# power.net
KiCad netlist of a schematic drawn in Altium Designer
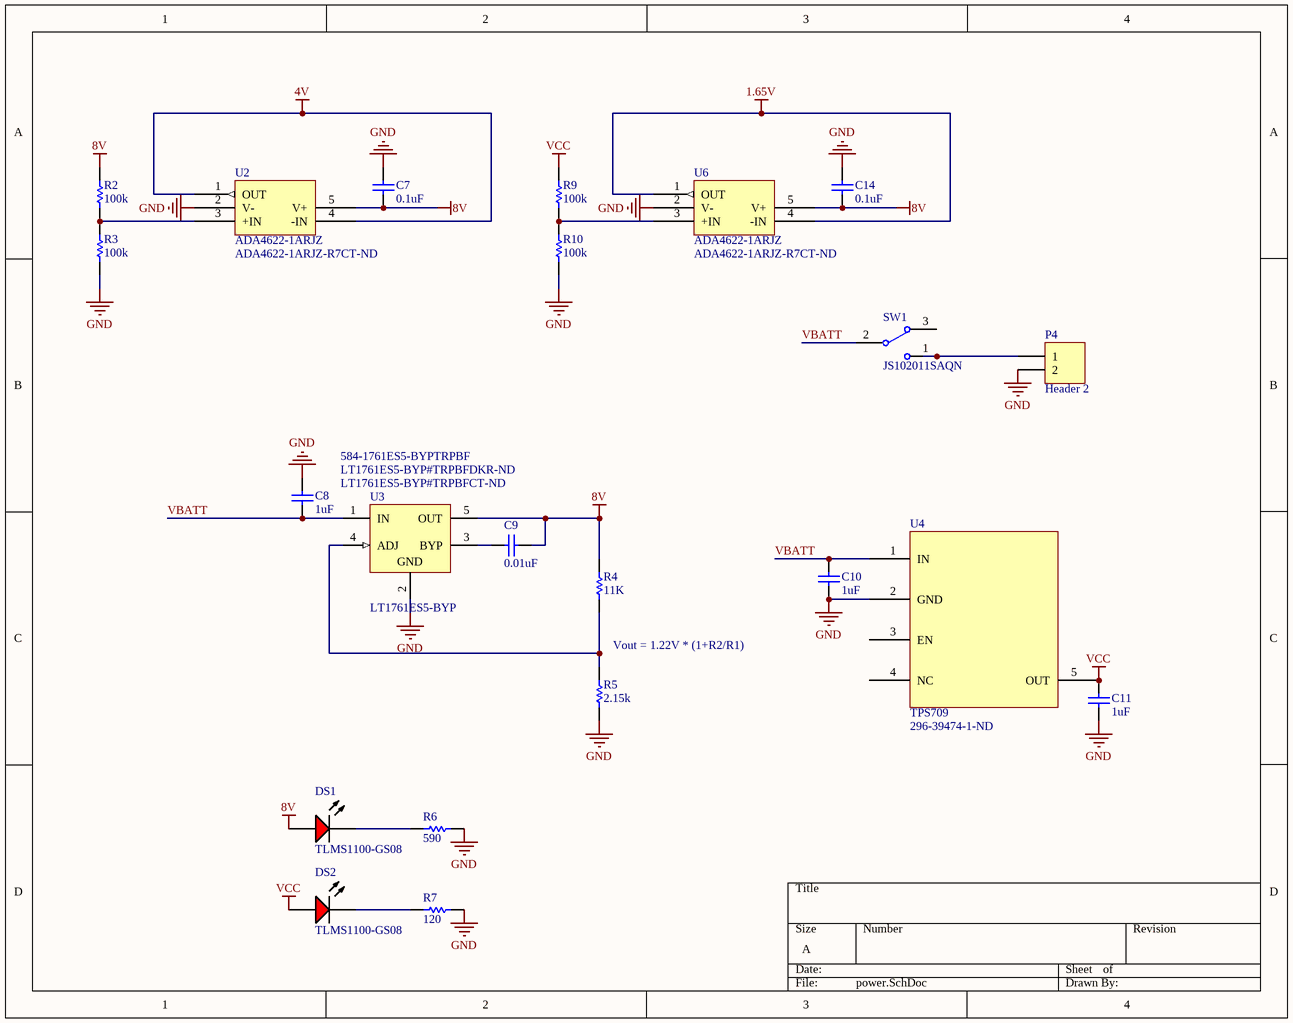
[diagram p0: power.SchDoc]

(export (version "E")
  (design (tool "Eeschema 10.0.6"))
  (components
    (comp (ref "C7")
      (value "0.1uF")
      (footprint "0603")
      (description "Ceramic Capacitor (Surface Mount)")
      (fields (field (name "MANUFACTURER") "Generic Ceramic Chip Cap (TBD)") (field (name "Comment") "Cap"))
      (libsource (lib "maglib") (part "Cap"))
    )
    (comp (ref "C8")
      (value "1uF")
      (footprint "0603")
      (description "Ceramic Capacitor (Surface Mount)")
      (fields (field (name "MANUFACTURER") "Generic Ceramic Chip Cap (TBD)") (field (name "Comment") "Cap"))
      (libsource (lib "maglib") (part "Cap"))
    )
    (comp (ref "C9")
      (value "0.01uF")
      (footprint "0603")
      (description "Ceramic Capacitor (Surface Mount)")
      (fields (field (name "MANUFACTURER") "Generic Ceramic Chip Cap (TBD)") (field (name "Comment") "Cap"))
      (libsource (lib "maglib") (part "Cap"))
    )
    (comp (ref "C10")
      (value "1uF")
      (footprint "0603")
      (description "Ceramic Capacitor (Surface Mount)")
      (fields (field (name "MANUFACTURER") "Generic Ceramic Chip Cap (TBD)") (field (name "Comment") "Cap"))
      (libsource (lib "maglib") (part "Cap"))
    )
    (comp (ref "C11")
      (value "1uF")
      (footprint "0603")
      (description "Ceramic Capacitor (Surface Mount)")
      (fields (field (name "MANUFACTURER") "Generic Ceramic Chip Cap (TBD)") (field (name "Comment") "Cap"))
      (libsource (lib "maglib") (part "Cap"))
    )
    (comp (ref "C14")
      (value "0.1uF")
      (footprint "0603")
      (description "Ceramic Capacitor (Surface Mount)")
      (fields (field (name "MANUFACTURER") "Generic Ceramic Chip Cap (TBD)") (field (name "Comment") "Cap"))
      (libsource (lib "maglib") (part "Cap"))
    )
    (comp (ref "DS1")
      (value "TLMS1100-GS08")
      (footprint "VISH-TLMX1100_V")
      (description "LED, RED, 2.1 V, -40 to 100 degC, 2-Pin SMD (0603), RoHS, Tape and Reel")
      (fields (field (name "TOLERANCE") "5%"))
      (libsource (lib "Altium Content Vault") (part "LED-RED-AK-2"))
    )
    (comp (ref "DS2")
      (value "TLMS1100-GS08")
      (footprint "VISH-TLMX1100_V")
      (description "LED, RED, 2.1 V, -40 to 100 degC, 2-Pin SMD (0603), RoHS, Tape and Reel")
      (fields (field (name "TOLERANCE") "5%"))
      (libsource (lib "Altium Content Vault") (part "LED-RED-AK-2"))
    )
    (comp (ref "P4")
      (value "Header 2")
      (footprint "HDR1X2")
      (description "Header, 2-Pin")
      (fields (field (name "PUBLISHER") "Altium Limited"))
      (libsource (lib "Miscellaneous Connectors") (part "Header 2"))
    )
    (comp (ref "R2")
      (value "100k")
      (footprint "0603")
      (description "Chip Resistor (Surface Mount)")
      (fields (field (name "MANUFACTURER") "Generic Chip Res (TBD)") (field (name "Comment") "Res"))
      (libsource (lib "maglib") (part "Res"))
    )
    (comp (ref "R3")
      (value "100k")
      (footprint "0603")
      (description "Chip Resistor (Surface Mount)")
      (fields (field (name "MANUFACTURER") "Generic Chip Res (TBD)") (field (name "Comment") "Res"))
      (libsource (lib "maglib") (part "Res"))
    )
    (comp (ref "R4")
      (value "11K")
      (footprint "0603")
      (description "Chip Resistor (Surface Mount)")
      (fields (field (name "MANUFACTURER") "Generic Chip Res (TBD)") (field (name "Comment") "Res"))
      (libsource (lib "maglib") (part "Res"))
    )
    (comp (ref "R5")
      (value "2.15k")
      (footprint "0603")
      (description "Chip Resistor (Surface Mount)")
      (fields (field (name "MANUFACTURER") "Generic Chip Res (TBD)") (field (name "Comment") "Res"))
      (libsource (lib "maglib") (part "Res"))
    )
    (comp (ref "R6")
      (value "590")
      (footprint "0603")
      (description "Chip Resistor (Surface Mount)")
      (fields (field (name "MANUFACTURER") "Generic Chip Res (TBD)") (field (name "Comment") "Res"))
      (libsource (lib "maglib") (part "Res"))
    )
    (comp (ref "R7")
      (value "120")
      (footprint "0603")
      (description "Chip Resistor (Surface Mount)")
      (fields (field (name "MANUFACTURER") "Generic Chip Res (TBD)") (field (name "Comment") "Res"))
      (libsource (lib "maglib") (part "Res"))
    )
    (comp (ref "R9")
      (value "100k")
      (footprint "0603")
      (description "Chip Resistor (Surface Mount)")
      (fields (field (name "MANUFACTURER") "Generic Chip Res (TBD)") (field (name "Comment") "Res"))
      (libsource (lib "maglib") (part "Res"))
    )
    (comp (ref "R10")
      (value "100k")
      (footprint "0603")
      (description "Chip Resistor (Surface Mount)")
      (fields (field (name "MANUFACTURER") "Generic Chip Res (TBD)") (field (name "Comment") "Res"))
      (libsource (lib "maglib") (part "Res"))
    )
    (comp (ref "SW1")
      (value "JS102011SAQN")
      (footprint "CKCP-JS102011SAQN-3_V")
      (description "Sub-Miniature Slide Switch, SPDT, -40 to 85 degC, 3-Pin SMD, RoHS, Tape and Reel")
      (fields (field (name "MANUFACTURER") "C&K Components"))
      (libsource (lib "Altium Content Vault") (part "SW-SPDT-3"))
    )
    (comp (ref "U2")
      (value "ADA4622-1ARJZ")
      (footprint "SOT95P280X145-5N")
      (description "30 V, 8 MHz, Low Bias Current,\r\nSingle-Supply, RRO, Precision Op Amps")
      (fields (field (name "SUPPLIER PART NUMBER 1") "ADA4622-1ARJZ-R7CT-ND"))
      (libsource (lib "maglib") (part "ADA4622-1ARJZ"))
    )
    (comp (ref "U3")
      (value "LT1761ES5-BYP")
      (footprint "LT-S5-5-TSOT-23_N")
      (fields
        (field (name "MANUFACTURER") "Linear Technology")
        (field (name "SUPPLIER PART NUMBER 1") "LT1761ES5-BYP#TRPBFCT-ND")
        (field (name "SUPPLIER PART NUMBER 2") "LT1761ES5-BYP#TRPBFDKR-ND")
        (field (name "SUPPLIER PART NUMBER 3") "584-1761ES5-BYPTRPBF")
      )
      (libsource (lib "Altium Content Vault") (part "LT-LTX1XXX-S5-5_C"))
    )
    (comp (ref "U4")
      (value "TPS709")
      (footprint "SOT95P280X145-5N")
      (description "3.3V Ultra low power Voltage Regulator")
      (fields (field (name "SUPPLIER PART NUMBER 1") "296-39474-1-ND"))
      (libsource (lib "maglib") (part "TPS70933"))
    )
    (comp (ref "U6")
      (value "ADA4622-1ARJZ")
      (footprint "SOT95P280X145-5N")
      (description "30 V, 8 MHz, Low Bias Current,\r\nSingle-Supply, RRO, Precision Op Amps")
      (fields (field (name "SUPPLIER PART NUMBER 1") "ADA4622-1ARJZ-R7CT-ND"))
      (libsource (lib "maglib") (part "ADA4622-1ARJZ"))
    )
  )
  (nets
    (net (code "1") (name "/VBATT") (class "Default")
      (node (ref "C10") (pin "1") (pinfunction "1_1") (pintype "passive"))
      (node (ref "C8") (pin "1") (pinfunction "1_1") (pintype "passive"))
      (node (ref "SW1") (pin "2") (pinfunction "2_2") (pintype "passive"))
      (node (ref "U3") (pin "1") (pinfunction "IN_1") (pintype "power_in"))
      (node (ref "U4") (pin "1") (pinfunction "IN_1") (pintype "passive"))
    )
    (net (code "2") (name "1.65V") (class "Default")
      (node (ref "U6") (pin "1") (pinfunction "OUT_1") (pintype "output"))
      (node (ref "U6") (pin "4") (pinfunction "-IN_4") (pintype "passive"))
    )
    (net (code "3") (name "4V") (class "Default")
      (node (ref "U2") (pin "1") (pinfunction "OUT_1") (pintype "output"))
      (node (ref "U2") (pin "4") (pinfunction "-IN_4") (pintype "passive"))
    )
    (net (code "4") (name "8V") (class "Default")
      (node (ref "C14") (pin "1") (pinfunction "1_1") (pintype "passive"))
      (node (ref "C7") (pin "1") (pinfunction "1_1") (pintype "passive"))
      (node (ref "C9") (pin "1") (pinfunction "1_1") (pintype "passive"))
      (node (ref "DS1") (pin "1") (pinfunction "A_1") (pintype "passive"))
      (node (ref "R2") (pin "2") (pinfunction "2_2") (pintype "passive"))
      (node (ref "R4") (pin "2") (pinfunction "2_2") (pintype "passive"))
      (node (ref "U2") (pin "5") (pinfunction "V+_5") (pintype "power_in"))
      (node (ref "U3") (pin "5") (pinfunction "OUT_5") (pintype "power_in"))
      (node (ref "U6") (pin "5") (pinfunction "V+_5") (pintype "power_in"))
    )
    (net (code "5") (name "GND") (class "Default")
      (node (ref "C10") (pin "2") (pinfunction "2_2") (pintype "passive"))
      (node (ref "C11") (pin "2") (pinfunction "2_2") (pintype "passive"))
      (node (ref "C14") (pin "2") (pinfunction "2_2") (pintype "passive"))
      (node (ref "C7") (pin "2") (pinfunction "2_2") (pintype "passive"))
      (node (ref "C8") (pin "2") (pinfunction "2_2") (pintype "passive"))
      (node (ref "P4") (pin "2") (pinfunction "2_2") (pintype "passive"))
      (node (ref "R10") (pin "1") (pinfunction "1_1") (pintype "passive"))
      (node (ref "R3") (pin "1") (pinfunction "1_1") (pintype "passive"))
      (node (ref "R5") (pin "1") (pinfunction "1_1") (pintype "passive"))
      (node (ref "R6") (pin "1") (pinfunction "1_1") (pintype "passive"))
      (node (ref "R7") (pin "1") (pinfunction "1_1") (pintype "passive"))
      (node (ref "U2") (pin "2") (pinfunction "V-_2") (pintype "power_in"))
      (node (ref "U3") (pin "2") (pinfunction "GND_2") (pintype "power_in"))
      (node (ref "U4") (pin "2") (pinfunction "GND_2") (pintype "passive"))
      (node (ref "U6") (pin "2") (pinfunction "V-_2") (pintype "power_in"))
    )
    (net (code "6") (name "Net-(DS1-K)") (class "Default")
      (node (ref "DS1") (pin "2") (pinfunction "K_2") (pintype "passive"))
      (node (ref "R6") (pin "2") (pinfunction "2_2") (pintype "passive"))
    )
    (net (code "7") (name "Net-(DS2-K)") (class "Default")
      (node (ref "DS2") (pin "2") (pinfunction "K_2") (pintype "passive"))
      (node (ref "R7") (pin "2") (pinfunction "2_2") (pintype "passive"))
    )
    (net (code "8") (name "Net-(P4-Pad1)") (class "Default")
      (node (ref "P4") (pin "1") (pinfunction "1_1") (pintype "passive"))
      (node (ref "SW1") (pin "1") (pinfunction "1_1") (pintype "passive"))
    )
    (net (code "9") (name "Net-(U2-+IN)") (class "Default")
      (node (ref "R2") (pin "1") (pinfunction "1_1") (pintype "passive"))
      (node (ref "R3") (pin "2") (pinfunction "2_2") (pintype "passive"))
      (node (ref "U2") (pin "3") (pinfunction "+IN_3") (pintype "passive"))
    )
    (net (code "10") (name "Net-(U3-ADJ)") (class "Default")
      (node (ref "R4") (pin "1") (pinfunction "1_1") (pintype "passive"))
      (node (ref "R5") (pin "2") (pinfunction "2_2") (pintype "passive"))
      (node (ref "U3") (pin "4") (pinfunction "ADJ_4") (pintype "input"))
    )
    (net (code "11") (name "Net-(U3-BYP)") (class "Default")
      (node (ref "C9") (pin "2") (pinfunction "2_2") (pintype "passive"))
      (node (ref "U3") (pin "3") (pinfunction "BYP_3") (pintype "passive"))
    )
    (net (code "12") (name "Net-(U6-+IN)") (class "Default")
      (node (ref "R10") (pin "2") (pinfunction "2_2") (pintype "passive"))
      (node (ref "R9") (pin "1") (pinfunction "1_1") (pintype "passive"))
      (node (ref "U6") (pin "3") (pinfunction "+IN_3") (pintype "passive"))
    )
    (net (code "13") (name "VCC") (class "Default")
      (node (ref "C11") (pin "1") (pinfunction "1_1") (pintype "passive"))
      (node (ref "DS2") (pin "1") (pinfunction "A_1") (pintype "passive"))
      (node (ref "R9") (pin "2") (pinfunction "2_2") (pintype "passive"))
      (node (ref "U4") (pin "5") (pinfunction "OUT_5") (pintype "passive"))
    )
    (net (code "14") (name "unconnected-(SW1-Pad3)") (class "Default")
      (node (ref "SW1") (pin "3") (pinfunction "3_3") (pintype "passive"))
    )
    (net (code "15") (name "unconnected-(U4-EN-Pad3)") (class "Default")
      (node (ref "U4") (pin "3") (pinfunction "EN_3") (pintype "passive"))
    )
    (net (code "16") (name "unconnected-(U4-NC-Pad4)") (class "Default")
      (node (ref "U4") (pin "4") (pinfunction "NC_4") (pintype "passive"))
    )
  )
)
